# rotaryboard.net
KiCad netlist of a schematic drawn in EAGLE
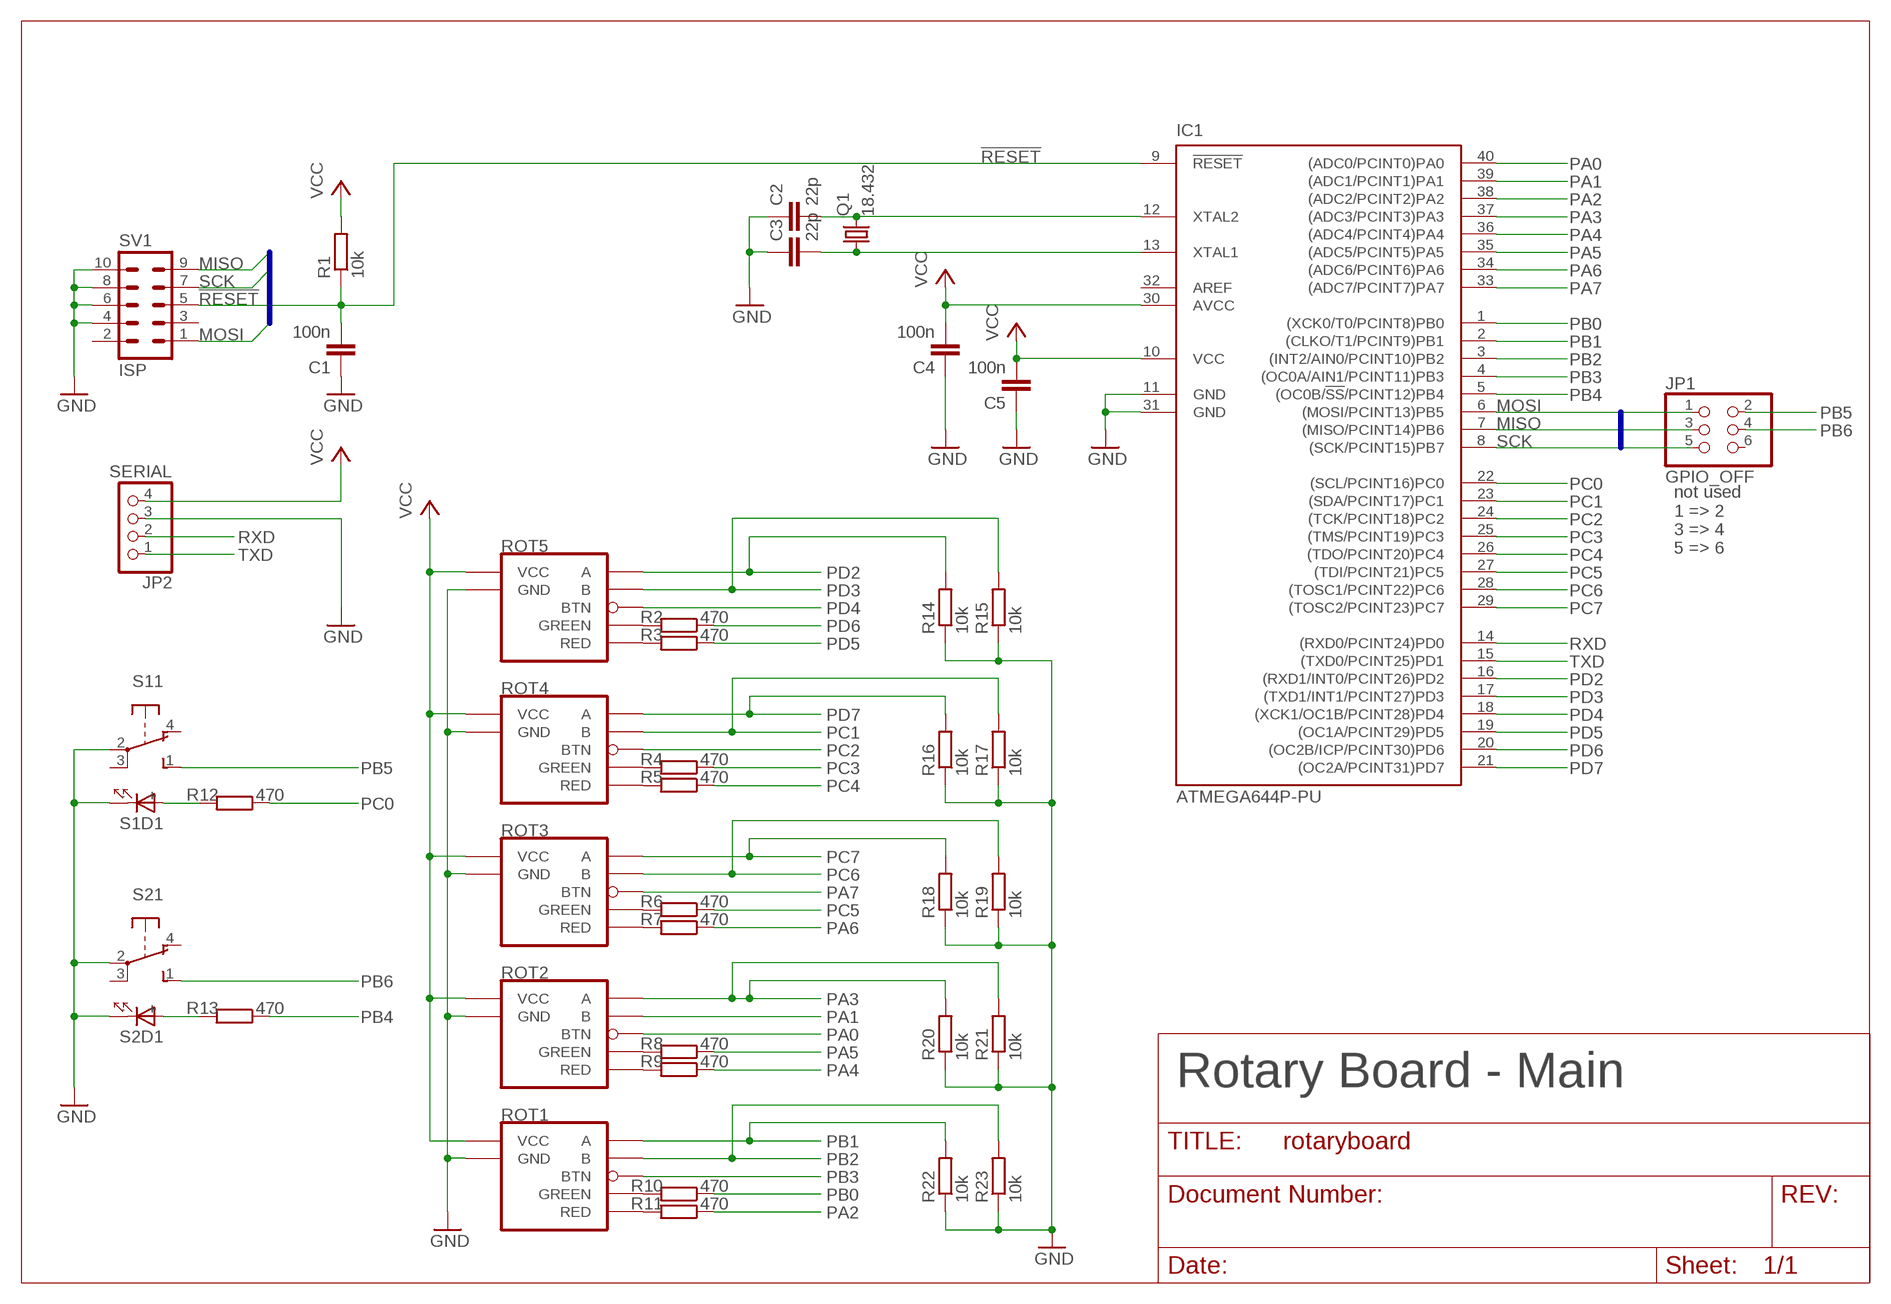
[diagram p0: schematic, sheet 1]

(export (version "E")
  (design (tool "Eeschema 10.0.6"))
  (components
    (comp (ref "C1")
      (value "100n")
      (footprint "eagle-import:C050-025X075")
      (libsource (lib "eagle-import") (part "C-EU050-025X075"))
    )
    (comp (ref "C2")
      (value "22p")
      (footprint "eagle-import:C050-025X075")
      (libsource (lib "eagle-import") (part "C-EU050-025X075"))
    )
    (comp (ref "C3")
      (value "22p")
      (footprint "eagle-import:C050-025X075")
      (libsource (lib "eagle-import") (part "C-EU050-025X075"))
    )
    (comp (ref "C4")
      (value "100n")
      (footprint "eagle-import:C050-025X075")
      (libsource (lib "eagle-import") (part "C-EU050-025X075"))
    )
    (comp (ref "C5")
      (value "100n")
      (footprint "eagle-import:C050-025X075")
      (libsource (lib "eagle-import") (part "C-EU050-025X075"))
    )
    (comp (ref "IC1")
      (value "ATMEGA644P-PU")
      (footprint "eagle-import:DIL40")
      (libsource (lib "eagle-import") (part "MEGA164P/324P/644P-PU"))
    )
    (comp (ref "JP1")
      (value "GPIO_OFF")
      (footprint "eagle-import:2X03")
      (libsource (lib "eagle-import") (part "PINHD-2X3"))
    )
    (comp (ref "JP2")
      (value "SERIAL")
      (footprint "eagle-import:1X04")
      (libsource (lib "eagle-import") (part "PINHD-1X4"))
    )
    (comp (ref "Q1")
      (value "18.432")
      (footprint "eagle-import:HC18U-V")
      (libsource (lib "eagle-import") (part "CRYSTALHC18U-V"))
    )
    (comp (ref "R1")
      (value "10k")
      (footprint "eagle-import:0207_10")
      (libsource (lib "eagle-import") (part "R-EU_0207/10"))
    )
    (comp (ref "R2")
      (value "470")
      (footprint "eagle-import:0207_10")
      (libsource (lib "eagle-import") (part "R-EU_0207/10"))
    )
    (comp (ref "R3")
      (value "470")
      (footprint "eagle-import:0207_10")
      (libsource (lib "eagle-import") (part "R-EU_0207/10"))
    )
    (comp (ref "R4")
      (value "470")
      (footprint "eagle-import:0207_10")
      (libsource (lib "eagle-import") (part "R-EU_0207/10"))
    )
    (comp (ref "R5")
      (value "470")
      (footprint "eagle-import:0207_10")
      (libsource (lib "eagle-import") (part "R-EU_0207/10"))
    )
    (comp (ref "R6")
      (value "470")
      (footprint "eagle-import:0207_10")
      (libsource (lib "eagle-import") (part "R-EU_0207/10"))
    )
    (comp (ref "R7")
      (value "470")
      (footprint "eagle-import:0207_10")
      (libsource (lib "eagle-import") (part "R-EU_0207/10"))
    )
    (comp (ref "R8")
      (value "470")
      (footprint "eagle-import:0207_10")
      (libsource (lib "eagle-import") (part "R-EU_0207/10"))
    )
    (comp (ref "R9")
      (value "470")
      (footprint "eagle-import:0207_10")
      (libsource (lib "eagle-import") (part "R-EU_0207/10"))
    )
    (comp (ref "R10")
      (value "470")
      (footprint "eagle-import:0207_10")
      (libsource (lib "eagle-import") (part "R-EU_0207/10"))
    )
    (comp (ref "R11")
      (value "470")
      (footprint "eagle-import:0207_10")
      (libsource (lib "eagle-import") (part "R-EU_0207/10"))
    )
    (comp (ref "R12")
      (value "470")
      (footprint "eagle-import:0207_10")
      (libsource (lib "eagle-import") (part "R-EU_0207/10"))
    )
    (comp (ref "R13")
      (value "470")
      (footprint "eagle-import:0207_10")
      (libsource (lib "eagle-import") (part "R-EU_0207/10"))
    )
    (comp (ref "R14")
      (value "10k")
      (footprint "eagle-import:0207_10")
      (libsource (lib "eagle-import") (part "R-EU_0207/10"))
    )
    (comp (ref "R15")
      (value "10k")
      (footprint "eagle-import:0207_10")
      (libsource (lib "eagle-import") (part "R-EU_0207/10"))
    )
    (comp (ref "R16")
      (value "10k")
      (footprint "eagle-import:0207_10")
      (libsource (lib "eagle-import") (part "R-EU_0207/10"))
    )
    (comp (ref "R17")
      (value "10k")
      (footprint "eagle-import:0207_10")
      (libsource (lib "eagle-import") (part "R-EU_0207/10"))
    )
    (comp (ref "R18")
      (value "10k")
      (footprint "eagle-import:0207_10")
      (libsource (lib "eagle-import") (part "R-EU_0207/10"))
    )
    (comp (ref "R19")
      (value "10k")
      (footprint "eagle-import:0207_10")
      (libsource (lib "eagle-import") (part "R-EU_0207/10"))
    )
    (comp (ref "R20")
      (value "10k")
      (footprint "eagle-import:0207_10")
      (libsource (lib "eagle-import") (part "R-EU_0207/10"))
    )
    (comp (ref "R21")
      (value "10k")
      (footprint "eagle-import:0207_10")
      (libsource (lib "eagle-import") (part "R-EU_0207/10"))
    )
    (comp (ref "R22")
      (value "10k")
      (footprint "eagle-import:0207_10")
      (libsource (lib "eagle-import") (part "R-EU_0207/10"))
    )
    (comp (ref "R23")
      (value "10k")
      (footprint "eagle-import:0207_10")
      (libsource (lib "eagle-import") (part "R-EU_0207/10"))
    )
    (comp (ref "ROT1")
      (value "DPL12SVCUSTOM")
      (footprint "eagle-import:DPL12SV")
      (libsource (lib "eagle-import") (part "DPL12SVCUSTOM"))
    )
    (comp (ref "ROT2")
      (value "DPL12SVCUSTOM")
      (footprint "eagle-import:DPL12SV")
      (libsource (lib "eagle-import") (part "DPL12SVCUSTOM"))
    )
    (comp (ref "ROT3")
      (value "DPL12SVCUSTOM")
      (footprint "eagle-import:DPL12SV")
      (libsource (lib "eagle-import") (part "DPL12SVCUSTOM"))
    )
    (comp (ref "ROT4")
      (value "DPL12SVCUSTOM")
      (footprint "eagle-import:DPL12SV")
      (libsource (lib "eagle-import") (part "DPL12SVCUSTOM"))
    )
    (comp (ref "ROT5")
      (value "DPL12SVCUSTOM")
      (footprint "eagle-import:DPL12SV")
      (libsource (lib "eagle-import") (part "DPL12SVCUSTOM"))
    )
    (comp (ref "S1")
      (value "SRKL")
      (footprint "eagle-import:SRKL")
      (libsource (lib "eagle-import") (part "SRKL"))
    )
    (comp (ref "S2")
      (value "SRKL")
      (footprint "eagle-import:SRKL")
      (libsource (lib "eagle-import") (part "SRKL"))
    )
    (comp (ref "SV1")
      (value "ISP")
      (footprint "eagle-import:ML10")
      (libsource (lib "eagle-import") (part "ML10"))
    )
  )
  (nets
    (net (code "1") (name "/AREF") (class "Default")
      (node (ref "IC1") (pin "32") (pinfunction "AREF_32") (pintype "power_in"))
    )
    (net (code "2") (name "/MISO") (class "Default")
      (node (ref "IC1") (pin "7") (pinfunction "(MISO/PCINT14)PB6_7") (pintype "bidirectional"))
      (node (ref "JP1") (pin "3") (pinfunction "3_3") (pintype "passive"))
      (node (ref "SV1") (pin "9") (pinfunction "9_9") (pintype "passive"))
    )
    (net (code "3") (name "/MOSI") (class "Default")
      (node (ref "IC1") (pin "6") (pinfunction "(MOSI/PCINT13)PB5_6") (pintype "bidirectional"))
      (node (ref "JP1") (pin "1") (pinfunction "1_1") (pintype "passive"))
      (node (ref "SV1") (pin "1") (pinfunction "1_1") (pintype "passive"))
    )
    (net (code "4") (name "/PA0") (class "Default")
      (node (ref "IC1") (pin "40") (pinfunction "(ADC0/PCINT0)PA0_40") (pintype "bidirectional"))
      (node (ref "ROT2") (pin "BTN") (pinfunction "BTN_BTN") (pintype "output"))
    )
    (net (code "5") (name "/PA1") (class "Default")
      (node (ref "IC1") (pin "39") (pinfunction "(ADC1/PCINT1)PA1_39") (pintype "bidirectional"))
      (node (ref "ROT2") (pin "B") (pinfunction "B_B") (pintype "output"))
    )
    (net (code "6") (name "/PA2") (class "Default")
      (node (ref "IC1") (pin "38") (pinfunction "(ADC2/PCINT2)PA2_38") (pintype "bidirectional"))
      (node (ref "R11") (pin "1") (pinfunction "1_1") (pintype "passive"))
    )
    (net (code "7") (name "/PA3") (class "Default")
      (node (ref "IC1") (pin "37") (pinfunction "(ADC3/PCINT3)PA3_37") (pintype "bidirectional"))
      (node (ref "R20") (pin "2") (pinfunction "2_2") (pintype "passive"))
      (node (ref "R21") (pin "2") (pinfunction "2_2") (pintype "passive"))
      (node (ref "ROT2") (pin "A") (pinfunction "A_A") (pintype "output"))
    )
    (net (code "8") (name "/PA4") (class "Default")
      (node (ref "IC1") (pin "36") (pinfunction "(ADC4/PCINT4)PA4_36") (pintype "bidirectional"))
      (node (ref "R9") (pin "1") (pinfunction "1_1") (pintype "passive"))
    )
    (net (code "9") (name "/PA5") (class "Default")
      (node (ref "IC1") (pin "35") (pinfunction "(ADC5/PCINT5)PA5_35") (pintype "bidirectional"))
      (node (ref "R8") (pin "1") (pinfunction "1_1") (pintype "passive"))
    )
    (net (code "10") (name "/PA6") (class "Default")
      (node (ref "IC1") (pin "34") (pinfunction "(ADC6/PCINT6)PA6_34") (pintype "bidirectional"))
      (node (ref "R7") (pin "1") (pinfunction "1_1") (pintype "passive"))
    )
    (net (code "11") (name "/PA7") (class "Default")
      (node (ref "IC1") (pin "33") (pinfunction "(ADC7/PCINT7)PA7_33") (pintype "bidirectional"))
      (node (ref "ROT3") (pin "BTN") (pinfunction "BTN_BTN") (pintype "output"))
    )
    (net (code "12") (name "/PB0") (class "Default")
      (node (ref "IC1") (pin "1") (pinfunction "(XCK0/T0/PCINT8)PB0_1") (pintype "bidirectional"))
      (node (ref "R10") (pin "1") (pinfunction "1_1") (pintype "passive"))
    )
    (net (code "13") (name "/PB1") (class "Default")
      (node (ref "IC1") (pin "2") (pinfunction "(CLKO/T1/PCINT9)PB1_2") (pintype "bidirectional"))
      (node (ref "R22") (pin "2") (pinfunction "2_2") (pintype "passive"))
      (node (ref "ROT1") (pin "A") (pinfunction "A_A") (pintype "output"))
    )
    (net (code "14") (name "/PB2") (class "Default")
      (node (ref "IC1") (pin "3") (pinfunction "(INT2/AIN0/PCINT10)PB2_3") (pintype "bidirectional"))
      (node (ref "R23") (pin "2") (pinfunction "2_2") (pintype "passive"))
      (node (ref "ROT1") (pin "B") (pinfunction "B_B") (pintype "output"))
    )
    (net (code "15") (name "/PB3") (class "Default")
      (node (ref "IC1") (pin "4") (pinfunction "(OC0A/AIN1/PCINT11)PB3_4") (pintype "bidirectional"))
      (node (ref "ROT1") (pin "BTN") (pinfunction "BTN_BTN") (pintype "output"))
    )
    (net (code "16") (name "/PB4") (class "Default")
      (node (ref "IC1") (pin "5") (pinfunction "(OC0B/~{SS}/PCINT12)PB4_5") (pintype "bidirectional"))
      (node (ref "R13") (pin "1") (pinfunction "1_1") (pintype "passive"))
    )
    (net (code "17") (name "/PB5") (class "Default")
      (node (ref "JP1") (pin "2") (pinfunction "2_2") (pintype "passive"))
      (node (ref "S1") (pin "1") (pinfunction "S_1") (pintype "passive"))
    )
    (net (code "18") (name "/PB6") (class "Default")
      (node (ref "JP1") (pin "4") (pinfunction "4_4") (pintype "passive"))
      (node (ref "S2") (pin "1") (pinfunction "S_1") (pintype "passive"))
    )
    (net (code "19") (name "/PC0") (class "Default")
      (node (ref "IC1") (pin "22") (pinfunction "(SCL/PCINT16)PC0_22") (pintype "bidirectional"))
      (node (ref "R12") (pin "1") (pinfunction "1_1") (pintype "passive"))
    )
    (net (code "20") (name "/PC1") (class "Default")
      (node (ref "IC1") (pin "23") (pinfunction "(SDA/PCINT17)PC1_23") (pintype "bidirectional"))
      (node (ref "R17") (pin "2") (pinfunction "2_2") (pintype "passive"))
      (node (ref "ROT4") (pin "B") (pinfunction "B_B") (pintype "output"))
    )
    (net (code "21") (name "/PC2") (class "Default")
      (node (ref "IC1") (pin "24") (pinfunction "(TCK/PCINT18)PC2_24") (pintype "bidirectional"))
      (node (ref "ROT4") (pin "BTN") (pinfunction "BTN_BTN") (pintype "output"))
    )
    (net (code "22") (name "/PC3") (class "Default")
      (node (ref "IC1") (pin "25") (pinfunction "(TMS/PCINT19)PC3_25") (pintype "bidirectional"))
      (node (ref "R4") (pin "1") (pinfunction "1_1") (pintype "passive"))
    )
    (net (code "23") (name "/PC4") (class "Default")
      (node (ref "IC1") (pin "26") (pinfunction "(TDO/PCINT20)PC4_26") (pintype "bidirectional"))
      (node (ref "R5") (pin "1") (pinfunction "1_1") (pintype "passive"))
    )
    (net (code "24") (name "/PC5") (class "Default")
      (node (ref "IC1") (pin "27") (pinfunction "(TDI/PCINT21)PC5_27") (pintype "bidirectional"))
      (node (ref "R6") (pin "1") (pinfunction "1_1") (pintype "passive"))
    )
    (net (code "25") (name "/PC6") (class "Default")
      (node (ref "IC1") (pin "28") (pinfunction "(TOSC1/PCINT22)PC6_28") (pintype "bidirectional"))
      (node (ref "R19") (pin "2") (pinfunction "2_2") (pintype "passive"))
      (node (ref "ROT3") (pin "B") (pinfunction "B_B") (pintype "output"))
    )
    (net (code "26") (name "/PC7") (class "Default")
      (node (ref "IC1") (pin "29") (pinfunction "(TOSC2/PCINT23)PC7_29") (pintype "bidirectional"))
      (node (ref "R18") (pin "2") (pinfunction "2_2") (pintype "passive"))
      (node (ref "ROT3") (pin "A") (pinfunction "A_A") (pintype "output"))
    )
    (net (code "27") (name "/PD2") (class "Default")
      (node (ref "IC1") (pin "16") (pinfunction "(RXD1/INT0/PCINT26)PD2_16") (pintype "bidirectional"))
      (node (ref "R14") (pin "2") (pinfunction "2_2") (pintype "passive"))
      (node (ref "ROT5") (pin "A") (pinfunction "A_A") (pintype "output"))
    )
    (net (code "28") (name "/PD3") (class "Default")
      (node (ref "IC1") (pin "17") (pinfunction "(TXD1/INT1/PCINT27)PD3_17") (pintype "bidirectional"))
      (node (ref "R15") (pin "2") (pinfunction "2_2") (pintype "passive"))
      (node (ref "ROT5") (pin "B") (pinfunction "B_B") (pintype "output"))
    )
    (net (code "29") (name "/PD4") (class "Default")
      (node (ref "IC1") (pin "18") (pinfunction "(XCK1/OC1B/PCINT28)PD4_18") (pintype "bidirectional"))
      (node (ref "ROT5") (pin "BTN") (pinfunction "BTN_BTN") (pintype "output"))
    )
    (net (code "30") (name "/PD5") (class "Default")
      (node (ref "IC1") (pin "19") (pinfunction "(OC1A/PCINT29)PD5_19") (pintype "bidirectional"))
      (node (ref "R3") (pin "1") (pinfunction "1_1") (pintype "passive"))
    )
    (net (code "31") (name "/PD6") (class "Default")
      (node (ref "IC1") (pin "20") (pinfunction "(OC2B/ICP/PCINT30)PD6_20") (pintype "bidirectional"))
      (node (ref "R2") (pin "1") (pinfunction "1_1") (pintype "passive"))
    )
    (net (code "32") (name "/PD7") (class "Default")
      (node (ref "IC1") (pin "21") (pinfunction "(OC2A/PCINT31)PD7_21") (pintype "bidirectional"))
      (node (ref "R16") (pin "2") (pinfunction "2_2") (pintype "passive"))
      (node (ref "ROT4") (pin "A") (pinfunction "A_A") (pintype "output"))
    )
    (net (code "33") (name "/RXD") (class "Default")
      (node (ref "IC1") (pin "14") (pinfunction "(RXD0/PCINT24)PD0_14") (pintype "bidirectional"))
      (node (ref "JP2") (pin "2") (pinfunction "2_2") (pintype "passive"))
    )
    (net (code "34") (name "/SCK") (class "Default")
      (node (ref "IC1") (pin "8") (pinfunction "(SCK/PCINT15)PB7_8") (pintype "bidirectional"))
      (node (ref "JP1") (pin "5") (pinfunction "5_5") (pintype "passive"))
      (node (ref "SV1") (pin "7") (pinfunction "7_7") (pintype "passive"))
    )
    (net (code "35") (name "/TXD") (class "Default")
      (node (ref "IC1") (pin "15") (pinfunction "(TXD0/PCINT25)PD1_15") (pintype "bidirectional"))
      (node (ref "JP2") (pin "1") (pinfunction "1_1") (pintype "passive"))
    )
    (net (code "36") (name "/~{RESET}") (class "Default")
      (node (ref "C1") (pin "2") (pinfunction "2_2") (pintype "passive"))
      (node (ref "IC1") (pin "9") (pinfunction "~{RESET}_9") (pintype "input"))
      (node (ref "R1") (pin "1") (pinfunction "1_1") (pintype "passive"))
      (node (ref "SV1") (pin "5") (pinfunction "5_5") (pintype "passive"))
    )
    (net (code "37") (name "GND") (class "Default")
      (node (ref "C1") (pin "1") (pinfunction "1_1") (pintype "passive"))
      (node (ref "C2") (pin "1") (pinfunction "1_1") (pintype "passive"))
      (node (ref "C3") (pin "1") (pinfunction "1_1") (pintype "passive"))
      (node (ref "C4") (pin "1") (pinfunction "1_1") (pintype "passive"))
      (node (ref "C5") (pin "1") (pinfunction "1_1") (pintype "passive"))
      (node (ref "IC1") (pin "11") (pinfunction "GND_11") (pintype "power_in"))
      (node (ref "IC1") (pin "31") (pinfunction "GND_31") (pintype "power_in"))
      (node (ref "JP2") (pin "3") (pinfunction "3_3") (pintype "passive"))
      (node (ref "R14") (pin "1") (pinfunction "1_1") (pintype "passive"))
      (node (ref "R15") (pin "1") (pinfunction "1_1") (pintype "passive"))
      (node (ref "R16") (pin "1") (pinfunction "1_1") (pintype "passive"))
      (node (ref "R17") (pin "1") (pinfunction "1_1") (pintype "passive"))
      (node (ref "R18") (pin "1") (pinfunction "1_1") (pintype "passive"))
      (node (ref "R19") (pin "1") (pinfunction "1_1") (pintype "passive"))
      (node (ref "R20") (pin "1") (pinfunction "1_1") (pintype "passive"))
      (node (ref "R21") (pin "1") (pinfunction "1_1") (pintype "passive"))
      (node (ref "R22") (pin "1") (pinfunction "1_1") (pintype "passive"))
      (node (ref "R23") (pin "1") (pinfunction "1_1") (pintype "passive"))
      (node (ref "ROT1") (pin "GND") (pinfunction "GND_GND") (pintype "power_in"))
      (node (ref "ROT2") (pin "GND") (pinfunction "GND_GND") (pintype "power_in"))
      (node (ref "ROT3") (pin "GND") (pinfunction "GND_GND") (pintype "power_in"))
      (node (ref "ROT4") (pin "GND") (pinfunction "GND_GND") (pintype "power_in"))
      (node (ref "ROT5") (pin "GND") (pinfunction "GND_GND") (pintype "power_in"))
      (node (ref "S1") (pin "-") (pinfunction "C_-") (pintype "passive"))
      (node (ref "S1") (pin "2") (pinfunction "P_2") (pintype "passive"))
      (node (ref "S2") (pin "-") (pinfunction "C_-") (pintype "passive"))
      (node (ref "S2") (pin "2") (pinfunction "P_2") (pintype "passive"))
      (node (ref "SV1") (pin "10") (pinfunction "10_10") (pintype "passive"))
      (node (ref "SV1") (pin "4") (pinfunction "4_4") (pintype "passive"))
      (node (ref "SV1") (pin "6") (pinfunction "6_6") (pintype "passive"))
      (node (ref "SV1") (pin "8") (pinfunction "8_8") (pintype "passive"))
    )
    (net (code "38") (name "Net-(IC1-XTAL1)") (class "Default")
      (node (ref "C3") (pin "2") (pinfunction "2_2") (pintype "passive"))
      (node (ref "IC1") (pin "13") (pinfunction "XTAL1_13") (pintype "input"))
      (node (ref "Q1") (pin "1") (pinfunction "1_1") (pintype "passive"))
    )
    (net (code "39") (name "Net-(IC1-XTAL2)") (class "Default")
      (node (ref "C2") (pin "2") (pinfunction "2_2") (pintype "passive"))
      (node (ref "IC1") (pin "12") (pinfunction "XTAL2_12") (pintype "output"))
      (node (ref "Q1") (pin "2") (pinfunction "2_2") (pintype "passive"))
    )
    (net (code "40") (name "Net-(R2-Pad2)") (class "Default")
      (node (ref "R2") (pin "2") (pinfunction "2_2") (pintype "passive"))
      (node (ref "ROT5") (pin "GREEN") (pinfunction "GREEN_GREEN") (pintype "passive"))
    )
    (net (code "41") (name "Net-(R3-Pad2)") (class "Default")
      (node (ref "R3") (pin "2") (pinfunction "2_2") (pintype "passive"))
      (node (ref "ROT5") (pin "RED") (pinfunction "RED_RED") (pintype "passive"))
    )
    (net (code "42") (name "Net-(R4-Pad2)") (class "Default")
      (node (ref "R4") (pin "2") (pinfunction "2_2") (pintype "passive"))
      (node (ref "ROT4") (pin "GREEN") (pinfunction "GREEN_GREEN") (pintype "passive"))
    )
    (net (code "43") (name "Net-(R5-Pad2)") (class "Default")
      (node (ref "R5") (pin "2") (pinfunction "2_2") (pintype "passive"))
      (node (ref "ROT4") (pin "RED") (pinfunction "RED_RED") (pintype "passive"))
    )
    (net (code "44") (name "Net-(R6-Pad2)") (class "Default")
      (node (ref "R6") (pin "2") (pinfunction "2_2") (pintype "passive"))
      (node (ref "ROT3") (pin "GREEN") (pinfunction "GREEN_GREEN") (pintype "passive"))
    )
    (net (code "45") (name "Net-(R7-Pad2)") (class "Default")
      (node (ref "R7") (pin "2") (pinfunction "2_2") (pintype "passive"))
      (node (ref "ROT3") (pin "RED") (pinfunction "RED_RED") (pintype "passive"))
    )
    (net (code "46") (name "Net-(R8-Pad2)") (class "Default")
      (node (ref "R8") (pin "2") (pinfunction "2_2") (pintype "passive"))
      (node (ref "ROT2") (pin "GREEN") (pinfunction "GREEN_GREEN") (pintype "passive"))
    )
    (net (code "47") (name "Net-(R9-Pad2)") (class "Default")
      (node (ref "R9") (pin "2") (pinfunction "2_2") (pintype "passive"))
      (node (ref "ROT2") (pin "RED") (pinfunction "RED_RED") (pintype "passive"))
    )
    (net (code "48") (name "Net-(R10-Pad2)") (class "Default")
      (node (ref "R10") (pin "2") (pinfunction "2_2") (pintype "passive"))
      (node (ref "ROT1") (pin "GREEN") (pinfunction "GREEN_GREEN") (pintype "passive"))
    )
    (net (code "49") (name "Net-(R11-Pad2)") (class "Default")
      (node (ref "R11") (pin "2") (pinfunction "2_2") (pintype "passive"))
      (node (ref "ROT1") (pin "RED") (pinfunction "RED_RED") (pintype "passive"))
    )
    (net (code "50") (name "Net-(S1B-A)") (class "Default")
      (node (ref "R12") (pin "2") (pinfunction "2_2") (pintype "passive"))
      (node (ref "S1") (pin "+") (pinfunction "A_+") (pintype "passive"))
    )
    (net (code "51") (name "Net-(S2B-A)") (class "Default")
      (node (ref "R13") (pin "2") (pinfunction "2_2") (pintype "passive"))
      (node (ref "S2") (pin "+") (pinfunction "A_+") (pintype "passive"))
    )
    (net (code "52") (name "VCC") (class "Default")
      (node (ref "C4") (pin "2") (pinfunction "2_2") (pintype "passive"))
      (node (ref "C5") (pin "2") (pinfunction "2_2") (pintype "passive"))
      (node (ref "IC1") (pin "10") (pinfunction "VCC_10") (pintype "power_in"))
      (node (ref "IC1") (pin "30") (pinfunction "AVCC_30") (pintype "power_in"))
      (node (ref "JP2") (pin "4") (pinfunction "4_4") (pintype "passive"))
      (node (ref "R1") (pin "2") (pinfunction "2_2") (pintype "passive"))
      (node (ref "ROT1") (pin "VCC") (pinfunction "VCC_VCC") (pintype "power_in"))
      (node (ref "ROT2") (pin "VCC") (pinfunction "VCC_VCC") (pintype "power_in"))
      (node (ref "ROT3") (pin "VCC") (pinfunction "VCC_VCC") (pintype "power_in"))
      (node (ref "ROT4") (pin "VCC") (pinfunction "VCC_VCC") (pintype "power_in"))
      (node (ref "ROT5") (pin "VCC") (pinfunction "VCC_VCC") (pintype "power_in"))
    )
    (net (code "53") (name "unconnected-(JP1-Pad6)") (class "Default")
      (node (ref "JP1") (pin "6") (pinfunction "6_6") (pintype "passive"))
    )
    (net (code "54") (name "unconnected-(S1A-O-Pad4)") (class "Default")
      (node (ref "S1") (pin "4") (pinfunction "O_4") (pintype "passive"))
    )
    (net (code "55") (name "unconnected-(S1A-P-Pad3)") (class "Default")
      (node (ref "S1") (pin "3") (pinfunction "P_3") (pintype "passive"))
    )
    (net (code "56") (name "unconnected-(S2A-O-Pad4)") (class "Default")
      (node (ref "S2") (pin "4") (pinfunction "O_4") (pintype "passive"))
    )
    (net (code "57") (name "unconnected-(S2A-P-Pad3)") (class "Default")
      (node (ref "S2") (pin "3") (pinfunction "P_3") (pintype "passive"))
    )
    (net (code "58") (name "unconnected-(SV1-Pad2)") (class "Default")
      (node (ref "SV1") (pin "2") (pinfunction "2_2") (pintype "passive"))
    )
    (net (code "59") (name "unconnected-(SV1-Pad3)") (class "Default")
      (node (ref "SV1") (pin "3") (pinfunction "3_3") (pintype "passive"))
    )
  )
)
